# power_regulator_aux.net
KiCad netlist of a schematic drawn in Altium Designer
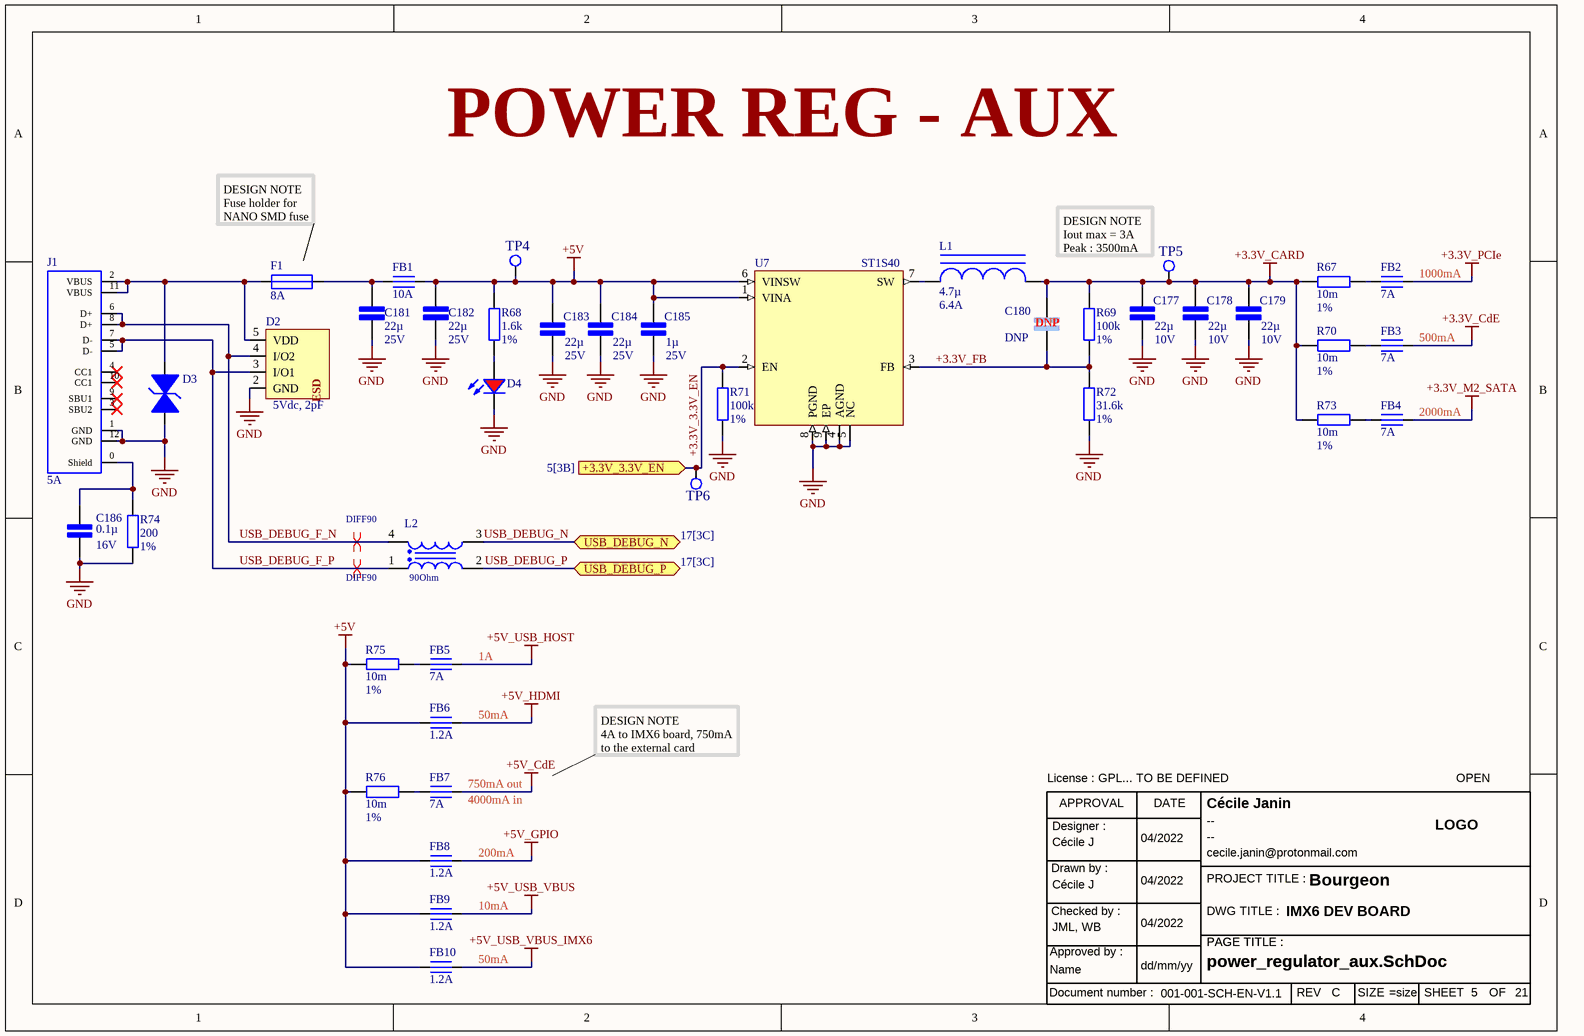
[diagram p0: power_regulator_aux.SchDoc]

(export (version "E")
  (design (tool "Eeschema 10.0.6"))
  (components
    (comp (ref "C177")
      (value "22µ")
      (footprint "Cap cer 0603/4608")
      (description "cap cer 22µ 10V 10% X5R 0603")
      (fields (field (name "TENSION DU DIÉLECTRIQUE") "10V"))
      (libsource (lib "First Board IMX6") (part "cap 22µ 10V"))
    )
    (comp (ref "C178")
      (value "22µ")
      (footprint "Cap cer 0603/4608")
      (description "cap cer 22µ 10V 10% X5R 0603")
      (fields (field (name "TENSION DU DIÉLECTRIQUE") "10V"))
      (libsource (lib "First Board IMX6") (part "cap 22µ 10V"))
    )
    (comp (ref "C179")
      (value "22µ")
      (footprint "Cap cer 0603/4608")
      (description "cap cer 22µ 10V 10% X5R 0603")
      (fields (field (name "TENSION DU DIÉLECTRIQUE") "10V"))
      (libsource (lib "First Board IMX6") (part "cap 22µ 10V"))
    )
    (comp (ref "C180")
      (value "DNP")
      (footprint "Cap cer 0402/1005")
      (description "cap cer DNP 0402")
      (libsource (lib "First Board IMX6") (part "cap DNP"))
    )
    (comp (ref "C181")
      (value "22µ")
      (footprint "Cap cer 0805/2012")
      (description "cap cer 22µ 25V 10% X5R 0805")
      (fields (field (name "TENSION DU DIÉLECTRIQUE") "25V"))
      (libsource (lib "First Board IMX6") (part "cap 22µ 25V"))
    )
    (comp (ref "C182")
      (value "22µ")
      (footprint "Cap cer 0805/2012")
      (description "cap cer 22µ 25V 10% X5R 0805")
      (fields (field (name "TENSION DU DIÉLECTRIQUE") "25V"))
      (libsource (lib "First Board IMX6") (part "cap 22µ 25V"))
    )
    (comp (ref "C183")
      (value "22µ")
      (footprint "Cap cer 0805/2012")
      (description "cap cer 22µ 25V 10% X5R 0805")
      (fields (field (name "TENSION DU DIÉLECTRIQUE") "25V"))
      (libsource (lib "First Board IMX6") (part "cap 22µ 25V"))
    )
    (comp (ref "C184")
      (value "22µ")
      (footprint "Cap cer 0805/2012")
      (description "cap cer 22µ 25V 10% X5R 0805")
      (fields (field (name "TENSION DU DIÉLECTRIQUE") "25V"))
      (libsource (lib "First Board IMX6") (part "cap 22µ 25V"))
    )
    (comp (ref "C185")
      (value "1µ")
      (footprint "Cap cer 0402/1005")
      (description "cap cer 1µ 25V 10% X5R 0402")
      (fields (field (name "TENSION DU DIÉLECTRIQUE") "25V"))
      (libsource (lib "First Board IMX6") (part "cap 1µ 25V"))
    )
    (comp (ref "C186")
      (value "0.1µ")
      (footprint "Cap cer 0402/1005")
      (description "cap solid electrolyte 0.1µ 6.3V 10%")
      (fields (field (name "TENSION DU DIÉLECTRIQUE") "16V"))
      (libsource (lib "First Board IMX6") (part "cap 0.1µ 16V"))
    )
    (comp (ref "D2")
      (value "5Vdc, 2pF")
      (footprint "Sot-23-5")
      (description "WE-TVS TVS Diode – High Speed Series, SOT23-5L, 2+1 Channel, 5Vdc, 2pF")
      (fields
        (field (name "MANUFACTURER PART NUMBER") "824011")
        (field (name "MANUFACTURER") "Wurth Elektronik")
      )
      (libsource (lib "First Board IMX6") (part "TVS USB 824011"))
    )
    (comp (ref "D3")
      (value "TVS 5V")
      (footprint "inductor 0402/1005")
      (description "82357120050")
      (libsource (lib "First Board IMX6") (part "TVS suppressor 82357120050"))
    )
    (comp (ref "D4")
      (value "Red, 2V, 120deg")
      (footprint "LED red 0603")
      (description "WL-SMCC SMD Mono-color Chip LED Compact, size 0603, Red, 2V, 120deg 150060RS73220")
      (fields (field (name "PART NUMBER") "150060RS73220") (field (name "PUBLISHER") "Wurth Elektronik"))
      (libsource (lib "First Board IMX6") (part "LED Red 0603"))
    )
    (comp (ref "F1")
      (value "8A")
      (footprint "Fuse holder SMD 01550900M")
      (description "Fuse 6A SMD 2410 / NANO")
      (libsource (lib "First Board IMX6") (part "Fuse_8A_SMD"))
    )
    (comp (ref "FB1")
      (value "10A")
      (footprint "Ferrite SMD 1612")
      (description "ferrite bead 10A 2.5m Ohm\r\n74279223560")
      (libsource (lib "First Board IMX6") (part "Ferrite bead 1612"))
    )
    (comp (ref "FB2")
      (value "7A")
      (footprint "inductor 0603/1603")
      (description "ferrite bead 17AA 2mohm\r\n7426926222")
      (libsource (lib "First Board IMX6") (part "Ferrite bead 0603"))
    )
    (comp (ref "FB3")
      (value "7A")
      (footprint "inductor 0603/1603")
      (description "ferrite bead 17AA 2mohm\r\n7426926222")
      (libsource (lib "First Board IMX6") (part "Ferrite bead 0603"))
    )
    (comp (ref "FB4")
      (value "7A")
      (footprint "inductor 0603/1603")
      (description "ferrite bead 17AA 2mohm\r\n7426926222")
      (libsource (lib "First Board IMX6") (part "Ferrite bead 0603"))
    )
    (comp (ref "FB5")
      (value "7A")
      (footprint "inductor 0603/1603")
      (description "ferrite bead 17AA 2mohm\r\n7426926222")
      (libsource (lib "First Board IMX6") (part "Ferrite bead 0603"))
    )
    (comp (ref "FB6")
      (value "1.2A")
      (footprint "inductor 0402/1005")
      (description "ferrite bead 1.2A 70mohm\r\n74269242111")
      (libsource (lib "First Board IMX6") (part "Ferrite bead 0402"))
    )
    (comp (ref "FB7")
      (value "7A")
      (footprint "inductor 0603/1603")
      (description "ferrite bead 17AA 2mohm\r\n7426926222")
      (libsource (lib "First Board IMX6") (part "Ferrite bead 0603"))
    )
    (comp (ref "FB8")
      (value "1.2A")
      (footprint "inductor 0402/1005")
      (description "ferrite bead 1.2A 70mohm\r\n74269242111")
      (libsource (lib "First Board IMX6") (part "Ferrite bead 0402"))
    )
    (comp (ref "FB9")
      (value "1.2A")
      (footprint "inductor 0402/1005")
      (description "ferrite bead 1.2A 70mohm\r\n74269242111")
      (libsource (lib "First Board IMX6") (part "Ferrite bead 0402"))
    )
    (comp (ref "FB10")
      (value "1.2A")
      (footprint "inductor 0402/1005")
      (description "ferrite bead 1.2A 70mohm\r\n74269242111")
      (libsource (lib "First Board IMX6") (part "Ferrite bead 0402"))
    )
    (comp (ref "J1")
      (value "5A")
      (footprint "USB C 12 Pin EXT 629722000214")
      (description "629722000214 wurth connector, up to 5A, with bottom pads for more cables")
      (libsource (lib "First Board IMX6") (part "USB C 12 pin EXT 629722000214"))
    )
    (comp (ref "L1")
      (value "4.7µ")
      (footprint "inductor 4030 74438357047")
      (description "inductor 4.7µ 6.4A sat 4030\r\n74438357047")
      (fields (field (name "SATURATION") "6.4A"))
      (libsource (lib "First Board IMX6") (part "inductor 4.7µ 6.4A"))
    )
    (comp (ref "L2")
      (value "90Ohm")
      (footprint "inductor coupled usb 0603")
      (description "WE-CNSW SMT Common Mode Line Filter, size 0603, 90Ohm, 0.55A, 50V")
      (fields
        (field (name "MANUFACTURER PART NUMBER") "744230900")
        (field (name "MANUFACTURER") "Wurth Elektronik")
      )
      (libsource (lib "First Board IMX6") (part "inductor coupled USB"))
    )
    (comp (ref "R67")
      (value "10m")
      (footprint "Res 0603/1603")
      (description "res 10m 1% 0.33W 0603")
      (fields (field (name "POURCENTAGE") "1%"))
      (libsource (lib "First Board IMX6") (part "res 10m 1%"))
    )
    (comp (ref "R68")
      (value "1.6k")
      (footprint "Res 0402/1005")
      (description "res 1.6k 1% 0402")
      (fields (field (name "POURCENTAGE") "1%"))
      (libsource (lib "First Board IMX6") (part "res 1.6k 1%"))
    )
    (comp (ref "R69")
      (value "100k")
      (footprint "Res 0402/1005")
      (description "res 100k 1% 0402")
      (fields (field (name "POURCENTAGE") "1%"))
      (libsource (lib "First Board IMX6") (part "res 100k 1%"))
    )
    (comp (ref "R70")
      (value "10m")
      (footprint "Res 0603/1603")
      (description "res 10m 1% 0.33W 0603")
      (fields (field (name "POURCENTAGE") "1%"))
      (libsource (lib "First Board IMX6") (part "res 10m 1%"))
    )
    (comp (ref "R71")
      (value "100k")
      (footprint "Res 0402/1005")
      (description "res 100k 1% 0402")
      (fields (field (name "POURCENTAGE") "1%"))
      (libsource (lib "First Board IMX6") (part "res 100k 1%"))
    )
    (comp (ref "R72")
      (value "31.6k")
      (footprint "Res 0402/1005")
      (description "res 31.6k 1% 0402")
      (fields (field (name "POURCENTAGE") "1%"))
      (libsource (lib "First Board IMX6") (part "res 31.6k 1%"))
    )
    (comp (ref "R73")
      (value "10m")
      (footprint "Res 0603/1603")
      (description "res 10m 1% 0.33W 0603")
      (fields (field (name "POURCENTAGE") "1%"))
      (libsource (lib "First Board IMX6") (part "res 10m 1%"))
    )
    (comp (ref "R74")
      (value "200")
      (footprint "Res 0402/1005")
      (description "res 200 1% 0402")
      (fields (field (name "POURCENTAGE") "1%"))
      (libsource (lib "First Board IMX6") (part "res 200 1%"))
    )
    (comp (ref "R75")
      (value "10m")
      (footprint "Res 0603/1603")
      (description "res 10m 1% 0.33W 0603")
      (fields (field (name "POURCENTAGE") "1%"))
      (libsource (lib "First Board IMX6") (part "res 10m 1%"))
    )
    (comp (ref "R76")
      (value "10m")
      (footprint "Res 0603/1603")
      (description "res 10m 1% 0.33W 0603")
      (fields (field (name "POURCENTAGE") "1%"))
      (libsource (lib "First Board IMX6") (part "res 10m 1%"))
    )
    (comp (ref "TB6")
      (value "Title bloc ANSI modified")
      (libsource (lib "First Board IMX6") (part "Title bloc ANSI"))
    )
    (comp (ref "TP4")
      (value "Test Point")
      (footprint "testpoint 1mm")
      (description "Test point 1mm diameter")
      (libsource (lib "First Board IMX6") (part "Test Point"))
    )
    (comp (ref "TP5")
      (value "Test Point")
      (footprint "testpoint 1mm")
      (description "Test point 1mm diameter")
      (libsource (lib "First Board IMX6") (part "Test Point"))
    )
    (comp (ref "TP6")
      (value "Test Point")
      (footprint "testpoint 1mm")
      (description "Test point 1mm diameter")
      (libsource (lib "First Board IMX6") (part "Test Point"))
    )
    (comp (ref "U7")
      (value "ST1S40")
      (footprint "SON 4x4 ST1S40")
      (description "switching regulator")
      (libsource (lib "First Board IMX6") (part "IC ST1S40 QFN"))
    )
  )
  (nets
    (net (code "1") (name "+3.3V_CARD") (class "Default")
      (node (ref "C177") (pin "1") (pinfunction "3_1") (pintype "passive"))
      (node (ref "C178") (pin "1") (pinfunction "3_1") (pintype "passive"))
      (node (ref "C179") (pin "1") (pinfunction "3_1") (pintype "passive"))
      (node (ref "C180") (pin "1") (pinfunction "3_1") (pintype "passive"))
      (node (ref "L1") (pin "2") (pintype "passive"))
      (node (ref "R67") (pin "1") (pintype "passive"))
      (node (ref "R69") (pin "2") (pintype "passive"))
      (node (ref "R70") (pin "1") (pintype "passive"))
      (node (ref "R73") (pin "1") (pintype "passive"))
      (node (ref "TP5") (pin "1") (pinfunction "tp_1") (pintype "passive"))
    )
    (net (code "2") (name "+3.3V_CdE") (class "Default")
      (node (ref "FB3") (pin "2") (pinfunction "2_2") (pintype "passive"))
    )
    (net (code "3") (name "+3.3V_M2_SATA") (class "Default")
      (node (ref "FB4") (pin "2") (pinfunction "2_2") (pintype "passive"))
    )
    (net (code "4") (name "+3.3V_PCIe") (class "Default")
      (node (ref "FB2") (pin "2") (pinfunction "2_2") (pintype "passive"))
    )
    (net (code "5") (name "+5V") (class "Default")
      (node (ref "C182") (pin "1") (pinfunction "3_1") (pintype "passive"))
      (node (ref "C183") (pin "1") (pinfunction "3_1") (pintype "passive"))
      (node (ref "C184") (pin "1") (pinfunction "3_1") (pintype "passive"))
      (node (ref "C185") (pin "1") (pinfunction "3_1") (pintype "passive"))
      (node (ref "FB1") (pin "2") (pinfunction "2_2") (pintype "passive"))
      (node (ref "FB10") (pin "1") (pinfunction "1_1") (pintype "passive"))
      (node (ref "FB6") (pin "1") (pinfunction "1_1") (pintype "passive"))
      (node (ref "FB8") (pin "1") (pinfunction "1_1") (pintype "passive"))
      (node (ref "FB9") (pin "1") (pinfunction "1_1") (pintype "passive"))
      (node (ref "R68") (pin "2") (pintype "passive"))
      (node (ref "R75") (pin "1") (pintype "passive"))
      (node (ref "R76") (pin "1") (pintype "passive"))
      (node (ref "TP4") (pin "1") (pinfunction "tp_1") (pintype "passive"))
      (node (ref "U7") (pin "1") (pinfunction "VINA_1") (pintype "input"))
      (node (ref "U7") (pin "6") (pinfunction "VINSW_6") (pintype "input"))
    )
    (net (code "6") (name "+5V_CdE") (class "Default")
      (node (ref "FB7") (pin "2") (pinfunction "2_2") (pintype "passive"))
    )
    (net (code "7") (name "+5V_GPIO") (class "Default")
      (node (ref "FB8") (pin "2") (pinfunction "2_2") (pintype "passive"))
    )
    (net (code "8") (name "+5V_HDMI") (class "Default")
      (node (ref "FB6") (pin "2") (pinfunction "2_2") (pintype "passive"))
    )
    (net (code "9") (name "+5V_USB_HOST") (class "Default")
      (node (ref "FB5") (pin "2") (pinfunction "2_2") (pintype "passive"))
    )
    (net (code "10") (name "+5V_USB_VBUS") (class "Default")
      (node (ref "FB9") (pin "2") (pinfunction "2_2") (pintype "passive"))
    )
    (net (code "11") (name "+5V_USB_VBUS_IMX6") (class "Default")
      (node (ref "FB10") (pin "2") (pinfunction "2_2") (pintype "passive"))
    )
    (net (code "12") (name "/+3.3V_3.3V_EN") (class "Default")
      (node (ref "R71") (pin "2") (pintype "passive"))
      (node (ref "TP6") (pin "1") (pinfunction "tp_1") (pintype "passive"))
      (node (ref "U7") (pin "2") (pinfunction "EN_2") (pintype "input"))
    )
    (net (code "13") (name "/+3.3V_FB") (class "Default")
      (node (ref "C180") (pin "2") (pinfunction "4_2") (pintype "passive"))
      (node (ref "R69") (pin "1") (pintype "passive"))
      (node (ref "R72") (pin "2") (pintype "passive"))
      (node (ref "U7") (pin "3") (pinfunction "FB_3") (pintype "input"))
    )
    (net (code "14") (name "/USB_DEBUG_F_N") (class "Default")
      (node (ref "D2") (pin "4") (pinfunction "I/O2_4") (pintype "passive"))
      (node (ref "J1") (pin "6") (pinfunction "D+_6") (pintype "passive"))
      (node (ref "J1") (pin "8") (pinfunction "D+_8") (pintype "passive"))
      (node (ref "L2") (pin "4") (pinfunction "4_4") (pintype "passive"))
    )
    (net (code "15") (name "/USB_DEBUG_F_P") (class "Default")
      (node (ref "D2") (pin "3") (pinfunction "I/O1_3") (pintype "passive"))
      (node (ref "J1") (pin "5") (pinfunction "D-_5") (pintype "passive"))
      (node (ref "J1") (pin "7") (pinfunction "D-_7") (pintype "passive"))
      (node (ref "L2") (pin "1") (pinfunction "1_1") (pintype "passive"))
    )
    (net (code "16") (name "/USB_DEBUG_N") (class "Default")
      (node (ref "L2") (pin "3") (pinfunction "3_3") (pintype "passive"))
    )
    (net (code "17") (name "/USB_DEBUG_P") (class "Default")
      (node (ref "L2") (pin "2") (pinfunction "2_2") (pintype "passive"))
    )
    (net (code "18") (name "GND") (class "Default")
      (node (ref "C177") (pin "2") (pinfunction "4_2") (pintype "passive"))
      (node (ref "C178") (pin "2") (pinfunction "4_2") (pintype "passive"))
      (node (ref "C179") (pin "2") (pinfunction "4_2") (pintype "passive"))
      (node (ref "C181") (pin "2") (pinfunction "4_2") (pintype "passive"))
      (node (ref "C182") (pin "2") (pinfunction "4_2") (pintype "passive"))
      (node (ref "C183") (pin "2") (pinfunction "4_2") (pintype "passive"))
      (node (ref "C184") (pin "2") (pinfunction "4_2") (pintype "passive"))
      (node (ref "C185") (pin "2") (pinfunction "4_2") (pintype "passive"))
      (node (ref "C186") (pin "2") (pinfunction "4_2") (pintype "passive"))
      (node (ref "D2") (pin "2") (pinfunction "GND_2") (pintype "passive"))
      (node (ref "D3") (pin "2") (pintype "passive"))
      (node (ref "D4") (pin "1") (pinfunction "K_1") (pintype "passive"))
      (node (ref "J1") (pin "1") (pinfunction "GND_1") (pintype "passive"))
      (node (ref "J1") (pin "12") (pinfunction "GND_12") (pintype "passive"))
      (node (ref "R71") (pin "1") (pintype "passive"))
      (node (ref "R72") (pin "1") (pintype "passive"))
      (node (ref "R74") (pin "1") (pintype "passive"))
      (node (ref "U7") (pin "4") (pinfunction "AGND_4") (pintype "passive"))
      (node (ref "U7") (pin "5") (pinfunction "NC_5") (pintype "passive"))
      (node (ref "U7") (pin "8") (pinfunction "PGND_8") (pintype "input"))
      (node (ref "U7") (pin "9") (pinfunction "EP_9") (pintype "input"))
    )
    (net (code "19") (name "Net-(C181-3)") (class "Default")
      (node (ref "C181") (pin "1") (pinfunction "3_1") (pintype "passive"))
      (node (ref "F1") (pin "2") (pinfunction "2_2") (pintype "passive"))
      (node (ref "FB1") (pin "1") (pinfunction "1_1") (pintype "passive"))
    )
    (net (code "20") (name "Net-(C186-3)") (class "Default")
      (node (ref "C186") (pin "1") (pinfunction "3_1") (pintype "passive"))
      (node (ref "J1") (pin "0") (pinfunction "Shield_0") (pintype "passive"))
      (node (ref "R74") (pin "2") (pintype "passive"))
    )
    (net (code "21") (name "Net-(D2-VDD)") (class "Default")
      (node (ref "D2") (pin "5") (pinfunction "VDD_5") (pintype "passive"))
      (node (ref "D3") (pin "1") (pintype "passive"))
      (node (ref "F1") (pin "1") (pinfunction "1_1") (pintype "passive"))
      (node (ref "J1") (pin "11") (pinfunction "VBUS_11") (pintype "passive"))
      (node (ref "J1") (pin "2") (pinfunction "VBUS_2") (pintype "passive"))
    )
    (net (code "22") (name "Net-(D4-A)") (class "Default")
      (node (ref "D4") (pin "2") (pinfunction "A_2") (pintype "passive"))
      (node (ref "R68") (pin "1") (pintype "passive"))
    )
    (net (code "23") (name "Net-(FB2-Pad1)") (class "Default")
      (node (ref "FB2") (pin "1") (pinfunction "1_1") (pintype "passive"))
      (node (ref "R67") (pin "2") (pintype "passive"))
    )
    (net (code "24") (name "Net-(FB3-Pad1)") (class "Default")
      (node (ref "FB3") (pin "1") (pinfunction "1_1") (pintype "passive"))
      (node (ref "R70") (pin "2") (pintype "passive"))
    )
    (net (code "25") (name "Net-(FB4-Pad1)") (class "Default")
      (node (ref "FB4") (pin "1") (pinfunction "1_1") (pintype "passive"))
      (node (ref "R73") (pin "2") (pintype "passive"))
    )
    (net (code "26") (name "Net-(FB5-Pad1)") (class "Default")
      (node (ref "FB5") (pin "1") (pinfunction "1_1") (pintype "passive"))
      (node (ref "R75") (pin "2") (pintype "passive"))
    )
    (net (code "27") (name "Net-(FB7-Pad1)") (class "Default")
      (node (ref "FB7") (pin "1") (pinfunction "1_1") (pintype "passive"))
      (node (ref "R76") (pin "2") (pintype "passive"))
    )
    (net (code "28") (name "Net-(U7-SW)") (class "Default")
      (node (ref "L1") (pin "1") (pintype "passive"))
      (node (ref "U7") (pin "7") (pinfunction "SW_7") (pintype "output"))
    )
    (net (code "29") (name "unconnected-(J1-CC1-Pad4)") (class "Default")
      (node (ref "J1") (pin "4") (pinfunction "CC1_4") (pintype "passive+no_connect"))
    )
    (net (code "30") (name "unconnected-(J1-CC1-Pad10)") (class "Default")
      (node (ref "J1") (pin "10") (pinfunction "CC1_10") (pintype "passive+no_connect"))
    )
    (net (code "31") (name "unconnected-(J1-SBU1-Pad9)") (class "Default")
      (node (ref "J1") (pin "9") (pinfunction "SBU1_9") (pintype "passive+no_connect"))
    )
    (net (code "32") (name "unconnected-(J1-SBU2-Pad3)") (class "Default")
      (node (ref "J1") (pin "3") (pinfunction "SBU2_3") (pintype "passive+no_connect"))
    )
  )
)
